# left.net
KiCad netlist of a schematic drawn in EAGLE
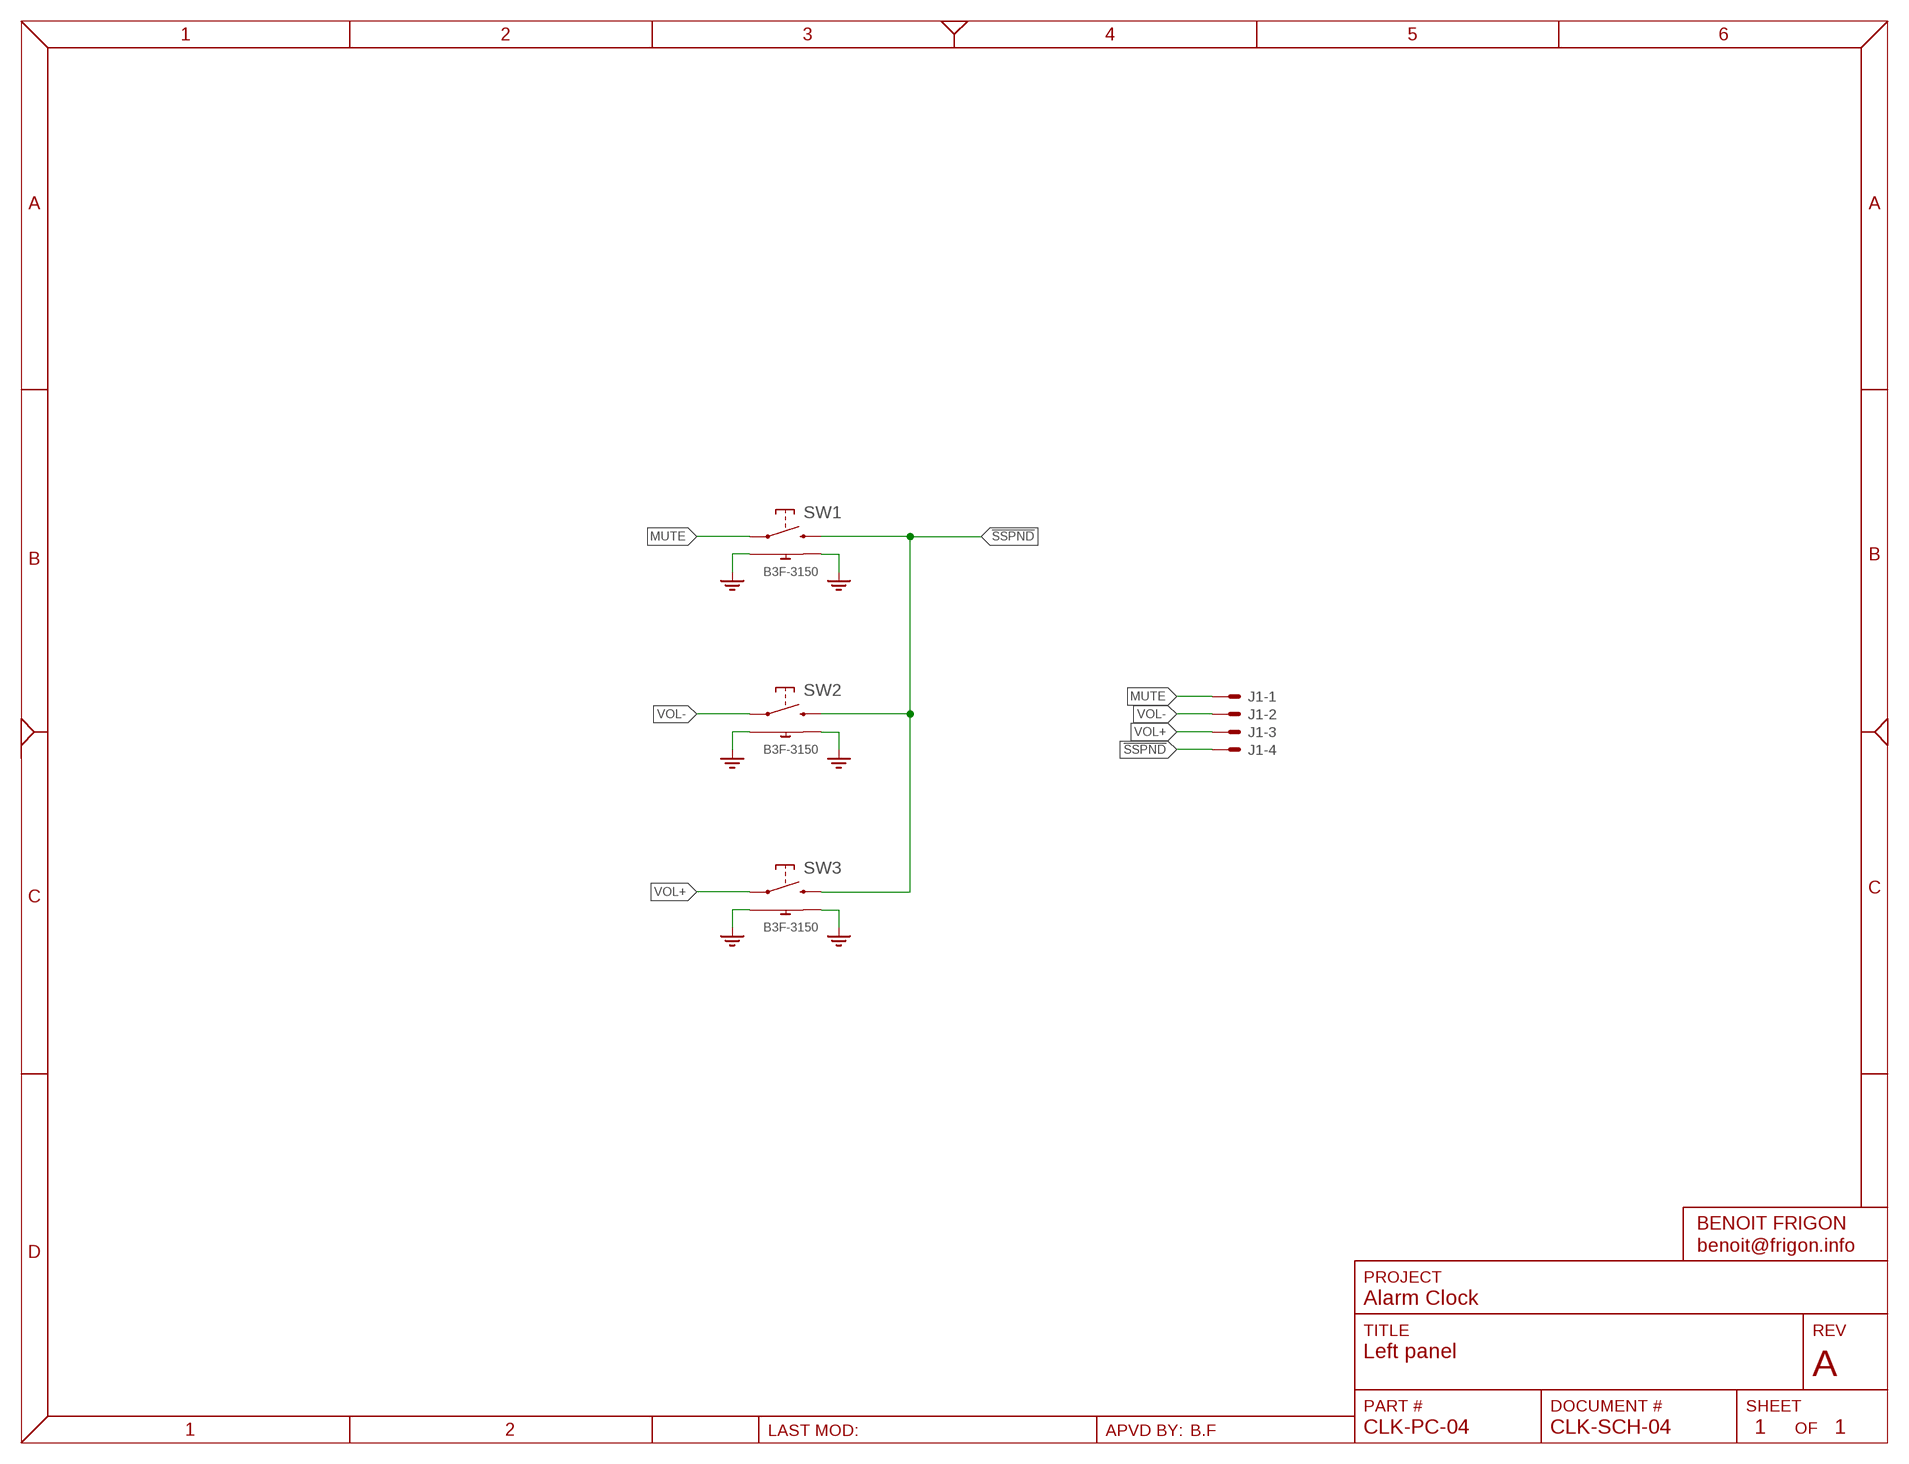
[diagram p0: schematic, sheet 1]

(export (version "E")
  (design (tool "Eeschema 10.0.6"))
  (components
    (comp (ref "J1")
      (value "SNG-2MM-HEADER-04-V")
      (footprint "eagle-import:DF3X-4P-2DSA")
      (fields (field (name "MFG") "Hirose Electronic"))
      (libsource (lib "eagle-import") (part "SNG-2MM-HEADER-04-V"))
    )
    (comp (ref "SW1")
      (value "B3F-3150")
      (footprint "eagle-import:B3F-315X")
      (fields (field (name "MFG") "Omron"))
      (libsource (lib "eagle-import") (part "B3F-315?0"))
    )
    (comp (ref "SW2")
      (value "B3F-3150")
      (footprint "eagle-import:B3F-315X")
      (fields (field (name "MFG") "Omron"))
      (libsource (lib "eagle-import") (part "B3F-315?0"))
    )
    (comp (ref "SW3")
      (value "B3F-3150")
      (footprint "eagle-import:B3F-315X")
      (fields (field (name "MFG") "Omron"))
      (libsource (lib "eagle-import") (part "B3F-315?0"))
    )
  )
  (nets
    (net (code "1") (name "/~{SSPND}") (class "Default")
      (node (ref "J1") (pin "4") (pinfunction "S_4") (pintype "bidirectional"))
      (node (ref "SW1") (pin "2") (pinfunction "2_2") (pintype "passive"))
      (node (ref "SW2") (pin "2") (pinfunction "2_2") (pintype "passive"))
      (node (ref "SW3") (pin "2") (pinfunction "2_2") (pintype "passive"))
    )
    (net (code "2") (name "GND") (class "Default")
      (node (ref "SW1") (pin "3") (pinfunction "3_3") (pintype "passive"))
      (node (ref "SW1") (pin "4") (pinfunction "4_4") (pintype "passive"))
      (node (ref "SW2") (pin "3") (pinfunction "3_3") (pintype "passive"))
      (node (ref "SW2") (pin "4") (pinfunction "4_4") (pintype "passive"))
      (node (ref "SW3") (pin "3") (pinfunction "3_3") (pintype "passive"))
      (node (ref "SW3") (pin "4") (pinfunction "4_4") (pintype "passive"))
    )
    (net (code "3") (name "MUTE") (class "Default")
      (node (ref "J1") (pin "1") (pinfunction "S_1") (pintype "bidirectional"))
      (node (ref "SW1") (pin "1") (pinfunction "1_1") (pintype "passive"))
    )
    (net (code "4") (name "VOL+") (class "Default")
      (node (ref "J1") (pin "3") (pinfunction "S_3") (pintype "bidirectional"))
      (node (ref "SW3") (pin "1") (pinfunction "1_1") (pintype "passive"))
    )
    (net (code "5") (name "VOL-") (class "Default")
      (node (ref "J1") (pin "2") (pinfunction "S_2") (pintype "bidirectional"))
      (node (ref "SW2") (pin "1") (pinfunction "1_1") (pintype "passive"))
    )
  )
)
